# AK8975.net
KiCad netlist of a schematic drawn in Altium Designer
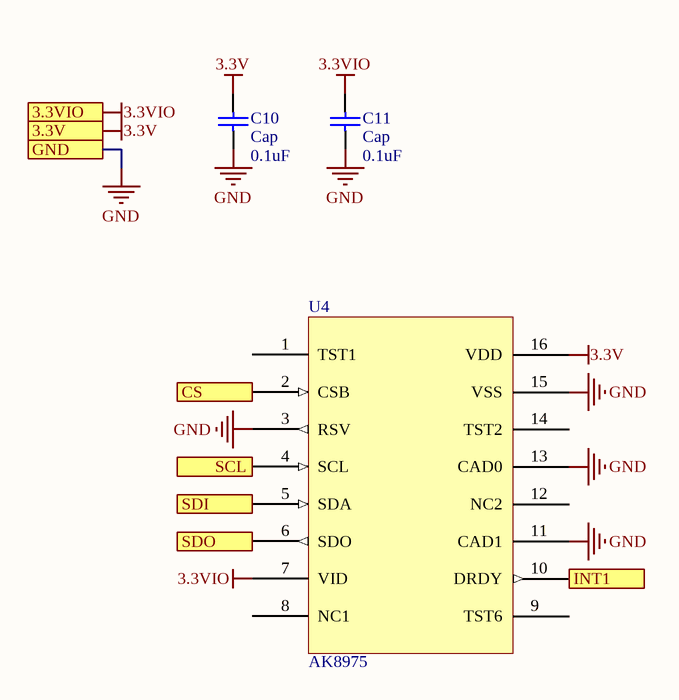
[diagram p0: AK8975.SchDoc]

(export (version "E")
  (design (tool "Eeschema 10.0.6"))
  (components
    (comp (ref "C10")
      (value "Cap")
      (footprint "0603")
      (description "Capacitor")
      (fields (field (name "ALTIUM_VALUE") "0.1uF") (field (name "PUBLISHER") "Altium Limited"))
      (libsource (lib "Miscellaneous Devices") (part "Cap"))
    )
    (comp (ref "C11")
      (value "Cap")
      (footprint "0603")
      (description "Capacitor")
      (fields (field (name "ALTIUM_VALUE") "0.1uF") (field (name "PUBLISHER") "Altium Limited"))
      (libsource (lib "Miscellaneous Devices") (part "Cap"))
    )
    (comp (ref "U4")
      (value "AK8975")
      (footprint "AK8975")
      (libsource (lib "altium-import") (part "root_0_AK8975_"))
    )
  )
  (nets
    (net (code "1") (name "/CS") (class "Default")
      (node (ref "U4") (pin "2") (pinfunction "CSB_2") (pintype "input"))
    )
    (net (code "2") (name "/INT1") (class "Default")
      (node (ref "U4") (pin "10") (pinfunction "DRDY_10") (pintype "output"))
    )
    (net (code "3") (name "/SCL") (class "Default")
      (node (ref "U4") (pin "4") (pinfunction "SCL_4") (pintype "input"))
    )
    (net (code "4") (name "/SDI") (class "Default")
      (node (ref "U4") (pin "5") (pinfunction "SDA_5") (pintype "input"))
    )
    (net (code "5") (name "/SDO") (class "Default")
      (node (ref "U4") (pin "6") (pinfunction "SDO_6") (pintype "output"))
    )
    (net (code "6") (name "3.3V") (class "Default")
      (node (ref "C10") (pin "1") (pinfunction "1_1") (pintype "passive"))
      (node (ref "U4") (pin "16") (pinfunction "VDD_16") (pintype "power_in"))
    )
    (net (code "7") (name "3.3VIO") (class "Default")
      (node (ref "C11") (pin "1") (pinfunction "1_1") (pintype "passive"))
      (node (ref "U4") (pin "7") (pinfunction "VID_7") (pintype "power_in"))
    )
    (net (code "8") (name "GND") (class "Default")
      (node (ref "C10") (pin "2") (pinfunction "2_2") (pintype "passive"))
      (node (ref "C11") (pin "2") (pinfunction "2_2") (pintype "passive"))
      (node (ref "U4") (pin "11") (pinfunction "CAD1_11") (pintype "passive"))
      (node (ref "U4") (pin "13") (pinfunction "CAD0_13") (pintype "passive"))
      (node (ref "U4") (pin "15") (pinfunction "VSS_15") (pintype "power_in"))
      (node (ref "U4") (pin "3") (pinfunction "RSV_3") (pintype "output"))
    )
    (net (code "9") (name "unconnected-(U4-NC1-Pad8)") (class "Default")
      (node (ref "U4") (pin "8") (pinfunction "NC1_8") (pintype "passive"))
    )
    (net (code "10") (name "unconnected-(U4-NC2-Pad12)") (class "Default")
      (node (ref "U4") (pin "12") (pinfunction "NC2_12") (pintype "passive"))
    )
    (net (code "11") (name "unconnected-(U4-TST1-Pad1)") (class "Default")
      (node (ref "U4") (pin "1") (pinfunction "TST1_1") (pintype "passive"))
    )
    (net (code "12") (name "unconnected-(U4-TST2-Pad14)") (class "Default")
      (node (ref "U4") (pin "14") (pinfunction "TST2_14") (pintype "passive"))
    )
    (net (code "13") (name "unconnected-(U4-TST6-Pad9)") (class "Default")
      (node (ref "U4") (pin "9") (pinfunction "TST6_9") (pintype "passive"))
    )
  )
)
